# ardcore.net
KiCad netlist of a schematic drawn in EAGLE
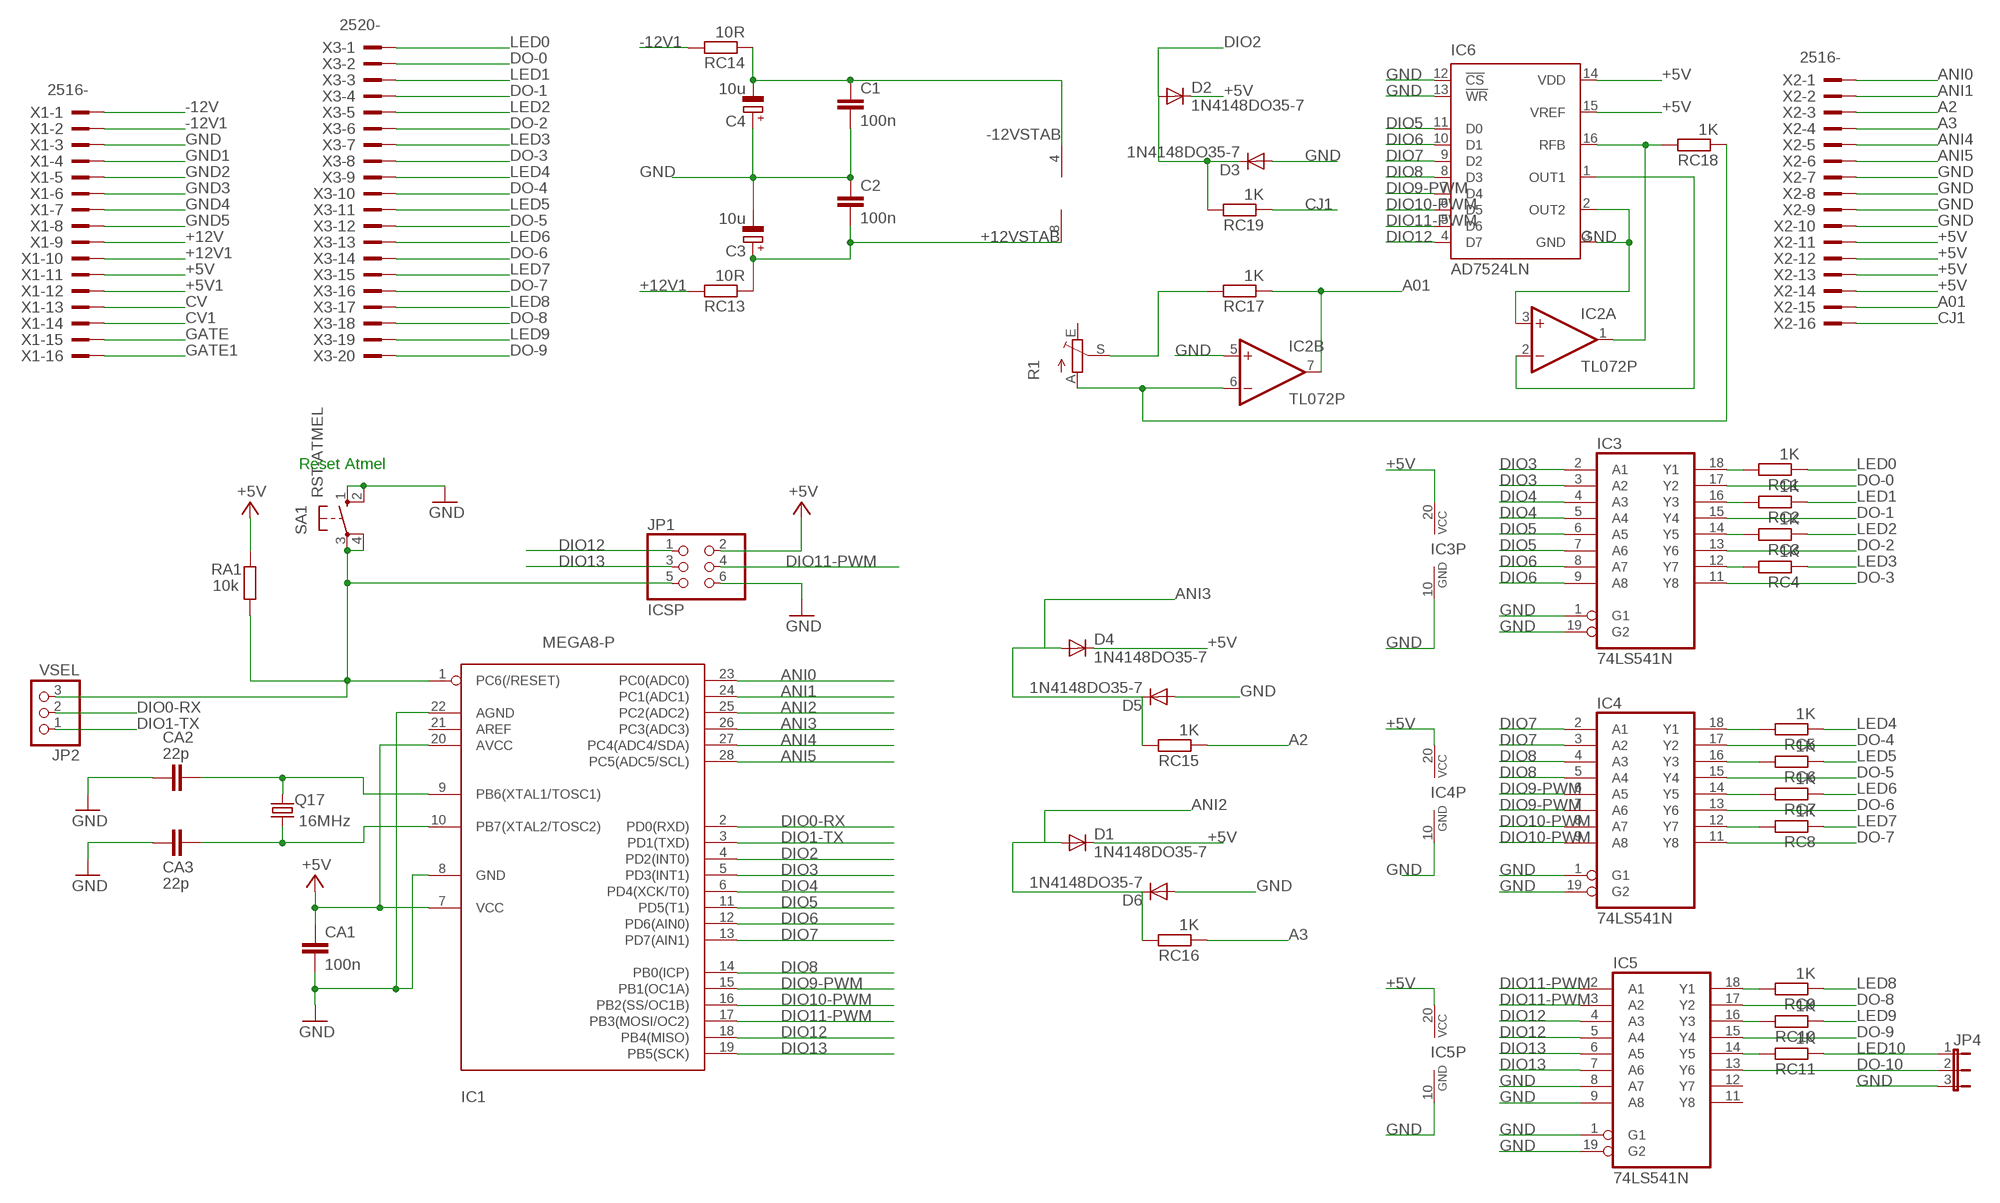
[diagram p0: schematic, sheet 1]

(export (version "E")
  (design (tool "Eeschema 10.0.6"))
  (components
    (comp (ref "C1")
      (value "100n")
      (footprint "eagle-import:C050-025X075")
      (libsource (lib "eagle-import") (part "C-EU050-025X075"))
    )
    (comp (ref "C2")
      (value "100n")
      (footprint "eagle-import:C050-025X075")
      (libsource (lib "eagle-import") (part "C-EU050-025X075"))
    )
    (comp (ref "C3")
      (value "10u")
      (footprint "eagle-import:E2,5-7")
      (libsource (lib "eagle-import") (part "CPOL-EUE2.5-7"))
    )
    (comp (ref "C4")
      (value "10u")
      (footprint "eagle-import:E2,5-7")
      (libsource (lib "eagle-import") (part "CPOL-EUE2.5-7"))
    )
    (comp (ref "CA1")
      (value "100n")
      (footprint "eagle-import:C050-025X075")
      (libsource (lib "eagle-import") (part "C-EU050-025X075"))
    )
    (comp (ref "CA2")
      (value "22p")
      (footprint "eagle-import:C050-025X075")
      (libsource (lib "eagle-import") (part "C-EU050-025X075"))
    )
    (comp (ref "CA3")
      (value "22p")
      (footprint "eagle-import:C050-025X075")
      (libsource (lib "eagle-import") (part "C-EU050-025X075"))
    )
    (comp (ref "D1")
      (value "1N4148DO35-7")
      (footprint "eagle-import:DO35-7")
      (libsource (lib "eagle-import") (part "1N4148DO35-7"))
    )
    (comp (ref "D2")
      (value "1N4148DO35-7")
      (footprint "eagle-import:DO35-7")
      (libsource (lib "eagle-import") (part "1N4148DO35-7"))
    )
    (comp (ref "D3")
      (value "1N4148DO35-7")
      (footprint "eagle-import:DO35-7")
      (libsource (lib "eagle-import") (part "1N4148DO35-7"))
    )
    (comp (ref "D4")
      (value "1N4148DO35-7")
      (footprint "eagle-import:DO35-7")
      (libsource (lib "eagle-import") (part "1N4148DO35-7"))
    )
    (comp (ref "D5")
      (value "1N4148DO35-7")
      (footprint "eagle-import:DO35-7")
      (libsource (lib "eagle-import") (part "1N4148DO35-7"))
    )
    (comp (ref "D6")
      (value "1N4148DO35-7")
      (footprint "eagle-import:DO35-7")
      (libsource (lib "eagle-import") (part "1N4148DO35-7"))
    )
    (comp (ref "IC1")
      (value "MEGA8-P")
      (footprint "eagle-import:DIL28-3")
      (libsource (lib "eagle-import") (part "MEGA8-P"))
    )
    (comp (ref "IC2")
      (value "TL072P")
      (footprint "eagle-import:DIL08")
      (libsource (lib "eagle-import") (part "TL072P"))
    )
    (comp (ref "IC3")
      (value "74LS541N")
      (footprint "eagle-import:DIL20")
      (libsource (lib "eagle-import") (part "74541NLS"))
    )
    (comp (ref "IC4")
      (value "74LS541N")
      (footprint "eagle-import:DIL20")
      (libsource (lib "eagle-import") (part "74541NLS"))
    )
    (comp (ref "IC5")
      (value "74LS541N")
      (footprint "eagle-import:DIL20")
      (libsource (lib "eagle-import") (part "74541NLS"))
    )
    (comp (ref "IC6")
      (value "AD7524LN")
      (footprint "eagle-import:DIL16")
      (fields (field (name "MF") "ALTERA CORPORATION") (field (name "MPN") "AD7524LNZ"))
      (libsource (lib "eagle-import") (part "AD7524NL"))
    )
    (comp (ref "JP1")
      (value "ICSP")
      (footprint "eagle-import:2X03")
      (libsource (lib "eagle-import") (part "PINHD-2X3"))
    )
    (comp (ref "JP2")
      (value "VSEL")
      (footprint "eagle-import:1X03")
      (libsource (lib "eagle-import") (part "PINHD-1X3"))
    )
    (comp (ref "JP4")
      (value "JP2E")
      (footprint "eagle-import:JP2")
      (libsource (lib "eagle-import") (part "JP2E"))
    )
    (comp (ref "Q17")
      (value "16MHz")
      (footprint "eagle-import:HC49_S")
      (libsource (lib "eagle-import") (part "CRYSTALHC49S"))
    )
    (comp (ref "R1")
      (value "TRIM_EU-B64Y")
      (footprint "eagle-import:B64Y")
      (libsource (lib "eagle-import") (part "TRIM_EU-B64Y"))
    )
    (comp (ref "RA1")
      (value "10k")
      (footprint "eagle-import:0207_10")
      (libsource (lib "eagle-import") (part "R-EU_0207/10"))
    )
    (comp (ref "RC1")
      (value "1K")
      (footprint "eagle-import:0207_10")
      (libsource (lib "eagle-import") (part "R-EU_0207/10"))
    )
    (comp (ref "RC2")
      (value "1K")
      (footprint "eagle-import:0207_10")
      (libsource (lib "eagle-import") (part "R-EU_0207/10"))
    )
    (comp (ref "RC3")
      (value "1K")
      (footprint "eagle-import:0207_10")
      (libsource (lib "eagle-import") (part "R-EU_0207/10"))
    )
    (comp (ref "RC4")
      (value "1K")
      (footprint "eagle-import:0207_10")
      (libsource (lib "eagle-import") (part "R-EU_0207/10"))
    )
    (comp (ref "RC5")
      (value "1K")
      (footprint "eagle-import:0207_10")
      (libsource (lib "eagle-import") (part "R-EU_0207/10"))
    )
    (comp (ref "RC6")
      (value "1K")
      (footprint "eagle-import:0207_10")
      (libsource (lib "eagle-import") (part "R-EU_0207/10"))
    )
    (comp (ref "RC7")
      (value "1K")
      (footprint "eagle-import:0207_10")
      (libsource (lib "eagle-import") (part "R-EU_0207/10"))
    )
    (comp (ref "RC8")
      (value "1K")
      (footprint "eagle-import:0207_10")
      (libsource (lib "eagle-import") (part "R-EU_0207/10"))
    )
    (comp (ref "RC9")
      (value "1K")
      (footprint "eagle-import:0207_10")
      (libsource (lib "eagle-import") (part "R-EU_0207/10"))
    )
    (comp (ref "RC10")
      (value "1K")
      (footprint "eagle-import:0207_10")
      (libsource (lib "eagle-import") (part "R-EU_0207/10"))
    )
    (comp (ref "RC11")
      (value "1K")
      (footprint "eagle-import:0207_10")
      (libsource (lib "eagle-import") (part "R-EU_0207/10"))
    )
    (comp (ref "RC13")
      (value "10R")
      (footprint "eagle-import:0207_10")
      (libsource (lib "eagle-import") (part "R-EU_0207/10"))
    )
    (comp (ref "RC14")
      (value "10R")
      (footprint "eagle-import:0207_10")
      (libsource (lib "eagle-import") (part "R-EU_0207/10"))
    )
    (comp (ref "RC15")
      (value "1K")
      (footprint "eagle-import:0207_10")
      (libsource (lib "eagle-import") (part "R-EU_0207/10"))
    )
    (comp (ref "RC16")
      (value "1K")
      (footprint "eagle-import:0207_10")
      (libsource (lib "eagle-import") (part "R-EU_0207/10"))
    )
    (comp (ref "RC17")
      (value "1K")
      (footprint "eagle-import:0207_10")
      (libsource (lib "eagle-import") (part "R-EU_0207/10"))
    )
    (comp (ref "RC18")
      (value "1K")
      (footprint "eagle-import:0207_10")
      (libsource (lib "eagle-import") (part "R-EU_0207/10"))
    )
    (comp (ref "RC19")
      (value "1K")
      (footprint "eagle-import:0207_10")
      (libsource (lib "eagle-import") (part "R-EU_0207/10"))
    )
    (comp (ref "SA1")
      (value "RST-ATMEL")
      (footprint "eagle-import:B3F-10XX")
      (libsource (lib "eagle-import") (part "10-XX"))
    )
    (comp (ref "X1")
      (value "2516-")
      (footprint "eagle-import:PAK100_2500-16")
      (libsource (lib "eagle-import") (part "2516-"))
    )
    (comp (ref "X2")
      (value "2516-")
      (footprint "eagle-import:PAK100_2500-16")
      (libsource (lib "eagle-import") (part "2516-"))
    )
    (comp (ref "X3")
      (value "2520-")
      (footprint "eagle-import:PAK100_2500-20")
      (libsource (lib "eagle-import") (part "2520-"))
    )
  )
  (nets
    (net (code "1") (name "+5V") (class "Default")
      (node (ref "CA1") (pin "1") (pinfunction "1_1") (pintype "passive"))
      (node (ref "D1") (pin "C") (pinfunction "C_C") (pintype "passive"))
      (node (ref "D2") (pin "C") (pinfunction "C_C") (pintype "passive"))
      (node (ref "D4") (pin "C") (pinfunction "C_C") (pintype "passive"))
      (node (ref "IC1") (pin "20") (pinfunction "AVCC_20") (pintype "power_in"))
      (node (ref "IC1") (pin "7") (pinfunction "VCC_7") (pintype "power_in"))
      (node (ref "IC3") (pin "20") (pinfunction "VCC_20") (pintype "power_in"))
      (node (ref "IC4") (pin "20") (pinfunction "VCC_20") (pintype "power_in"))
      (node (ref "IC5") (pin "20") (pinfunction "VCC_20") (pintype "power_in"))
      (node (ref "IC6") (pin "14") (pinfunction "VDD_14") (pintype "power_in"))
      (node (ref "IC6") (pin "15") (pinfunction "VREF_15") (pintype "input"))
      (node (ref "JP1") (pin "2") (pinfunction "2_2") (pintype "passive"))
      (node (ref "RA1") (pin "1") (pinfunction "1_1") (pintype "passive"))
      (node (ref "X1") (pin "11") (pinfunction "KL_11") (pintype "passive"))
      (node (ref "X2") (pin "11") (pinfunction "KL_11") (pintype "passive"))
      (node (ref "X2") (pin "12") (pinfunction "KL_12") (pintype "passive"))
      (node (ref "X2") (pin "13") (pinfunction "KL_13") (pintype "passive"))
      (node (ref "X2") (pin "14") (pinfunction "KL_14") (pintype "passive"))
    )
    (net (code "2") (name "/+5V1") (class "Default")
      (node (ref "X1") (pin "12") (pinfunction "KL_12") (pintype "passive"))
    )
    (net (code "3") (name "/+12V") (class "Default")
      (node (ref "X1") (pin "9") (pinfunction "KL_9") (pintype "passive"))
    )
    (net (code "4") (name "/+12V1") (class "Default")
      (node (ref "RC13") (pin "2") (pinfunction "2_2") (pintype "passive"))
      (node (ref "X1") (pin "10") (pinfunction "KL_10") (pintype "passive"))
    )
    (net (code "5") (name "/+12VSTAB") (class "Default")
      (node (ref "C2") (pin "2") (pinfunction "2_2") (pintype "passive"))
      (node (ref "C3") (pin "+") (pinfunction "+_+") (pintype "passive"))
      (node (ref "IC2") (pin "8") (pinfunction "V+_8") (pintype "power_in"))
      (node (ref "RC13") (pin "1") (pinfunction "1_1") (pintype "passive"))
    )
    (net (code "6") (name "/-12V") (class "Default")
      (node (ref "X1") (pin "1") (pinfunction "KL_1") (pintype "passive"))
    )
    (net (code "7") (name "/-12V1") (class "Default")
      (node (ref "RC14") (pin "2") (pinfunction "2_2") (pintype "passive"))
      (node (ref "X1") (pin "2") (pinfunction "KL_2") (pintype "passive"))
    )
    (net (code "8") (name "/-12VSTAB") (class "Default")
      (node (ref "C1") (pin "1") (pinfunction "1_1") (pintype "passive"))
      (node (ref "C4") (pin "-") (pinfunction "-_-") (pintype "passive"))
      (node (ref "IC2") (pin "4") (pinfunction "V-_4") (pintype "power_in"))
      (node (ref "RC14") (pin "1") (pinfunction "1_1") (pintype "passive"))
    )
    (net (code "9") (name "/A01") (class "Default")
      (node (ref "IC2") (pin "7") (pinfunction "OUT_7") (pintype "output"))
      (node (ref "RC17") (pin "1") (pinfunction "1_1") (pintype "passive"))
      (node (ref "X2") (pin "15") (pinfunction "KL_15") (pintype "passive"))
    )
    (net (code "10") (name "/A2") (class "Default")
      (node (ref "RC15") (pin "1") (pinfunction "1_1") (pintype "passive"))
      (node (ref "X2") (pin "3") (pinfunction "KL_3") (pintype "passive"))
    )
    (net (code "11") (name "/A3") (class "Default")
      (node (ref "RC16") (pin "1") (pinfunction "1_1") (pintype "passive"))
      (node (ref "X2") (pin "4") (pinfunction "KL_4") (pintype "passive"))
    )
    (net (code "12") (name "/ANI0") (class "Default")
      (node (ref "IC1") (pin "23") (pinfunction "PC0(ADC0)_23") (pintype "bidirectional"))
      (node (ref "X2") (pin "1") (pinfunction "KL_1") (pintype "passive"))
    )
    (net (code "13") (name "/ANI1") (class "Default")
      (node (ref "IC1") (pin "24") (pinfunction "PC1(ADC1)_24") (pintype "bidirectional"))
      (node (ref "X2") (pin "2") (pinfunction "KL_2") (pintype "passive"))
    )
    (net (code "14") (name "/ANI2") (class "Default")
      (node (ref "D1") (pin "A") (pinfunction "A_A") (pintype "passive"))
      (node (ref "D6") (pin "C") (pinfunction "C_C") (pintype "passive"))
      (node (ref "IC1") (pin "25") (pinfunction "PC2(ADC2)_25") (pintype "bidirectional"))
      (node (ref "RC16") (pin "2") (pinfunction "2_2") (pintype "passive"))
    )
    (net (code "15") (name "/ANI3") (class "Default")
      (node (ref "D4") (pin "A") (pinfunction "A_A") (pintype "passive"))
      (node (ref "D5") (pin "C") (pinfunction "C_C") (pintype "passive"))
      (node (ref "IC1") (pin "26") (pinfunction "PC3(ADC3)_26") (pintype "bidirectional"))
      (node (ref "RC15") (pin "2") (pinfunction "2_2") (pintype "passive"))
    )
    (net (code "16") (name "/ANI4") (class "Default")
      (node (ref "IC1") (pin "27") (pinfunction "PC4(ADC4/SDA)_27") (pintype "bidirectional"))
      (node (ref "X2") (pin "5") (pinfunction "KL_5") (pintype "passive"))
    )
    (net (code "17") (name "/ANI5") (class "Default")
      (node (ref "IC1") (pin "28") (pinfunction "PC5(ADC5/SCL)_28") (pintype "bidirectional"))
      (node (ref "X2") (pin "6") (pinfunction "KL_6") (pintype "passive"))
    )
    (net (code "18") (name "/CJ1") (class "Default")
      (node (ref "RC19") (pin "1") (pinfunction "1_1") (pintype "passive"))
      (node (ref "X2") (pin "16") (pinfunction "KL_16") (pintype "passive"))
    )
    (net (code "19") (name "/CV") (class "Default")
      (node (ref "X1") (pin "13") (pinfunction "KL_13") (pintype "passive"))
    )
    (net (code "20") (name "/CV1") (class "Default")
      (node (ref "X1") (pin "14") (pinfunction "KL_14") (pintype "passive"))
    )
    (net (code "21") (name "/DIO0-RX") (class "Default")
      (node (ref "IC1") (pin "2") (pinfunction "PD0(RXD)_2") (pintype "bidirectional"))
      (node (ref "JP2") (pin "2") (pinfunction "2_2") (pintype "passive"))
    )
    (net (code "22") (name "/DIO1-TX") (class "Default")
      (node (ref "IC1") (pin "3") (pinfunction "PD1(TXD)_3") (pintype "bidirectional"))
      (node (ref "JP2") (pin "1") (pinfunction "1_1") (pintype "passive"))
    )
    (net (code "23") (name "/DIO2") (class "Default")
      (node (ref "D2") (pin "A") (pinfunction "A_A") (pintype "passive"))
      (node (ref "D3") (pin "C") (pinfunction "C_C") (pintype "passive"))
      (node (ref "IC1") (pin "4") (pinfunction "PD2(INT0)_4") (pintype "bidirectional"))
      (node (ref "RC19") (pin "2") (pinfunction "2_2") (pintype "passive"))
    )
    (net (code "24") (name "/DIO3") (class "Default")
      (node (ref "IC1") (pin "5") (pinfunction "PD3(INT1)_5") (pintype "bidirectional"))
      (node (ref "IC3") (pin "2") (pinfunction "A1_2") (pintype "input"))
      (node (ref "IC3") (pin "3") (pinfunction "A2_3") (pintype "input"))
    )
    (net (code "25") (name "/DIO4") (class "Default")
      (node (ref "IC1") (pin "6") (pinfunction "PD4(XCK/T0)_6") (pintype "bidirectional"))
      (node (ref "IC3") (pin "4") (pinfunction "A3_4") (pintype "input"))
      (node (ref "IC3") (pin "5") (pinfunction "A4_5") (pintype "input"))
    )
    (net (code "26") (name "/DIO5") (class "Default")
      (node (ref "IC1") (pin "11") (pinfunction "PD5(T1)_11") (pintype "bidirectional"))
      (node (ref "IC3") (pin "6") (pinfunction "A5_6") (pintype "input"))
      (node (ref "IC3") (pin "7") (pinfunction "A6_7") (pintype "input"))
      (node (ref "IC6") (pin "11") (pinfunction "D0_11") (pintype "input"))
    )
    (net (code "27") (name "/DIO6") (class "Default")
      (node (ref "IC1") (pin "12") (pinfunction "PD6(AIN0)_12") (pintype "bidirectional"))
      (node (ref "IC3") (pin "8") (pinfunction "A7_8") (pintype "input"))
      (node (ref "IC3") (pin "9") (pinfunction "A8_9") (pintype "input"))
      (node (ref "IC6") (pin "10") (pinfunction "D1_10") (pintype "input"))
    )
    (net (code "28") (name "/DIO7") (class "Default")
      (node (ref "IC1") (pin "13") (pinfunction "PD7(AIN1)_13") (pintype "bidirectional"))
      (node (ref "IC4") (pin "2") (pinfunction "A1_2") (pintype "input"))
      (node (ref "IC4") (pin "3") (pinfunction "A2_3") (pintype "input"))
      (node (ref "IC6") (pin "9") (pinfunction "D2_9") (pintype "input"))
    )
    (net (code "29") (name "/DIO8") (class "Default")
      (node (ref "IC1") (pin "14") (pinfunction "PB0(ICP)_14") (pintype "bidirectional"))
      (node (ref "IC4") (pin "4") (pinfunction "A3_4") (pintype "input"))
      (node (ref "IC4") (pin "5") (pinfunction "A4_5") (pintype "input"))
      (node (ref "IC6") (pin "8") (pinfunction "D3_8") (pintype "input"))
    )
    (net (code "30") (name "/DIO9-PWM") (class "Default")
      (node (ref "IC1") (pin "15") (pinfunction "PB1(OC1A)_15") (pintype "bidirectional"))
      (node (ref "IC4") (pin "6") (pinfunction "A5_6") (pintype "input"))
      (node (ref "IC4") (pin "7") (pinfunction "A6_7") (pintype "input"))
      (node (ref "IC6") (pin "7") (pinfunction "D4_7") (pintype "input"))
    )
    (net (code "31") (name "/DIO10-PWM") (class "Default")
      (node (ref "IC1") (pin "16") (pinfunction "PB2(SS/OC1B)_16") (pintype "bidirectional"))
      (node (ref "IC4") (pin "8") (pinfunction "A7_8") (pintype "input"))
      (node (ref "IC4") (pin "9") (pinfunction "A8_9") (pintype "input"))
      (node (ref "IC6") (pin "6") (pinfunction "D5_6") (pintype "input"))
    )
    (net (code "32") (name "/DIO11-PWM") (class "Default")
      (node (ref "IC1") (pin "17") (pinfunction "PB3(MOSI/OC2)_17") (pintype "bidirectional"))
      (node (ref "IC5") (pin "2") (pinfunction "A1_2") (pintype "input"))
      (node (ref "IC5") (pin "3") (pinfunction "A2_3") (pintype "input"))
      (node (ref "IC6") (pin "5") (pinfunction "D6_5") (pintype "input"))
      (node (ref "JP1") (pin "4") (pinfunction "4_4") (pintype "passive"))
    )
    (net (code "33") (name "/DIO12") (class "Default")
      (node (ref "IC1") (pin "18") (pinfunction "PB4(MISO)_18") (pintype "bidirectional"))
      (node (ref "IC5") (pin "4") (pinfunction "A3_4") (pintype "input"))
      (node (ref "IC5") (pin "5") (pinfunction "A4_5") (pintype "input"))
      (node (ref "IC6") (pin "4") (pinfunction "D7_4") (pintype "input"))
      (node (ref "JP1") (pin "1") (pinfunction "1_1") (pintype "passive"))
    )
    (net (code "34") (name "/DIO13") (class "Default")
      (node (ref "IC1") (pin "19") (pinfunction "PB5(SCK)_19") (pintype "bidirectional"))
      (node (ref "IC5") (pin "6") (pinfunction "A5_6") (pintype "input"))
      (node (ref "IC5") (pin "7") (pinfunction "A6_7") (pintype "input"))
      (node (ref "JP1") (pin "3") (pinfunction "3_3") (pintype "passive"))
    )
    (net (code "35") (name "/DO-0") (class "Default")
      (node (ref "IC3") (pin "17") (pinfunction "Y2_17") (pintype "tri_state"))
      (node (ref "X3") (pin "2") (pinfunction "KL_2") (pintype "passive"))
    )
    (net (code "36") (name "/DO-1") (class "Default")
      (node (ref "IC3") (pin "15") (pinfunction "Y4_15") (pintype "tri_state"))
      (node (ref "X3") (pin "4") (pinfunction "KL_4") (pintype "passive"))
    )
    (net (code "37") (name "/DO-2") (class "Default")
      (node (ref "IC3") (pin "13") (pinfunction "Y6_13") (pintype "tri_state"))
      (node (ref "X3") (pin "6") (pinfunction "KL_6") (pintype "passive"))
    )
    (net (code "38") (name "/DO-3") (class "Default")
      (node (ref "IC3") (pin "11") (pinfunction "Y8_11") (pintype "tri_state"))
      (node (ref "X3") (pin "8") (pinfunction "KL_8") (pintype "passive"))
    )
    (net (code "39") (name "/DO-4") (class "Default")
      (node (ref "IC4") (pin "17") (pinfunction "Y2_17") (pintype "tri_state"))
      (node (ref "X3") (pin "10") (pinfunction "KL_10") (pintype "passive"))
    )
    (net (code "40") (name "/DO-5") (class "Default")
      (node (ref "IC4") (pin "15") (pinfunction "Y4_15") (pintype "tri_state"))
      (node (ref "X3") (pin "12") (pinfunction "KL_12") (pintype "passive"))
    )
    (net (code "41") (name "/DO-6") (class "Default")
      (node (ref "IC4") (pin "13") (pinfunction "Y6_13") (pintype "tri_state"))
      (node (ref "X3") (pin "14") (pinfunction "KL_14") (pintype "passive"))
    )
    (net (code "42") (name "/DO-7") (class "Default")
      (node (ref "IC4") (pin "11") (pinfunction "Y8_11") (pintype "tri_state"))
      (node (ref "X3") (pin "16") (pinfunction "KL_16") (pintype "passive"))
    )
    (net (code "43") (name "/DO-8") (class "Default")
      (node (ref "IC5") (pin "17") (pinfunction "Y2_17") (pintype "tri_state"))
      (node (ref "X3") (pin "18") (pinfunction "KL_18") (pintype "passive"))
    )
    (net (code "44") (name "/DO-9") (class "Default")
      (node (ref "IC5") (pin "15") (pinfunction "Y4_15") (pintype "tri_state"))
      (node (ref "X3") (pin "20") (pinfunction "KL_20") (pintype "passive"))
    )
    (net (code "45") (name "/DO-10") (class "Default")
      (node (ref "IC5") (pin "13") (pinfunction "Y6_13") (pintype "tri_state"))
      (node (ref "JP4") (pin "2") (pinfunction "2_2") (pintype "passive"))
    )
    (net (code "46") (name "/GATE") (class "Default")
      (node (ref "X1") (pin "15") (pinfunction "KL_15") (pintype "passive"))
    )
    (net (code "47") (name "/GATE1") (class "Default")
      (node (ref "X1") (pin "16") (pinfunction "KL_16") (pintype "passive"))
    )
    (net (code "48") (name "/GND1") (class "Default")
      (node (ref "X1") (pin "4") (pinfunction "KL_4") (pintype "passive"))
    )
    (net (code "49") (name "/GND2") (class "Default")
      (node (ref "X1") (pin "5") (pinfunction "KL_5") (pintype "passive"))
    )
    (net (code "50") (name "/GND3") (class "Default")
      (node (ref "X1") (pin "6") (pinfunction "KL_6") (pintype "passive"))
    )
    (net (code "51") (name "/GND4") (class "Default")
      (node (ref "X1") (pin "7") (pinfunction "KL_7") (pintype "passive"))
    )
    (net (code "52") (name "/GND5") (class "Default")
      (node (ref "X1") (pin "8") (pinfunction "KL_8") (pintype "passive"))
    )
    (net (code "53") (name "/LED0") (class "Default")
      (node (ref "RC1") (pin "1") (pinfunction "1_1") (pintype "passive"))
      (node (ref "X3") (pin "1") (pinfunction "KL_1") (pintype "passive"))
    )
    (net (code "54") (name "/LED1") (class "Default")
      (node (ref "RC2") (pin "1") (pinfunction "1_1") (pintype "passive"))
      (node (ref "X3") (pin "3") (pinfunction "KL_3") (pintype "passive"))
    )
    (net (code "55") (name "/LED2") (class "Default")
      (node (ref "RC3") (pin "1") (pinfunction "1_1") (pintype "passive"))
      (node (ref "X3") (pin "5") (pinfunction "KL_5") (pintype "passive"))
    )
    (net (code "56") (name "/LED3") (class "Default")
      (node (ref "RC4") (pin "1") (pinfunction "1_1") (pintype "passive"))
      (node (ref "X3") (pin "7") (pinfunction "KL_7") (pintype "passive"))
    )
    (net (code "57") (name "/LED4") (class "Default")
      (node (ref "RC5") (pin "1") (pinfunction "1_1") (pintype "passive"))
      (node (ref "X3") (pin "9") (pinfunction "KL_9") (pintype "passive"))
    )
    (net (code "58") (name "/LED5") (class "Default")
      (node (ref "RC6") (pin "1") (pinfunction "1_1") (pintype "passive"))
      (node (ref "X3") (pin "11") (pinfunction "KL_11") (pintype "passive"))
    )
    (net (code "59") (name "/LED6") (class "Default")
      (node (ref "RC7") (pin "1") (pinfunction "1_1") (pintype "passive"))
      (node (ref "X3") (pin "13") (pinfunction "KL_13") (pintype "passive"))
    )
    (net (code "60") (name "/LED7") (class "Default")
      (node (ref "RC8") (pin "1") (pinfunction "1_1") (pintype "passive"))
      (node (ref "X3") (pin "15") (pinfunction "KL_15") (pintype "passive"))
    )
    (net (code "61") (name "/LED8") (class "Default")
      (node (ref "RC9") (pin "1") (pinfunction "1_1") (pintype "passive"))
      (node (ref "X3") (pin "17") (pinfunction "KL_17") (pintype "passive"))
    )
    (net (code "62") (name "/LED9") (class "Default")
      (node (ref "RC10") (pin "1") (pinfunction "1_1") (pintype "passive"))
      (node (ref "X3") (pin "19") (pinfunction "KL_19") (pintype "passive"))
    )
    (net (code "63") (name "/LED10") (class "Default")
      (node (ref "JP4") (pin "1") (pinfunction "1_1") (pintype "passive"))
      (node (ref "RC11") (pin "1") (pinfunction "1_1") (pintype "passive"))
    )
    (net (code "64") (name "GND") (class "Default")
      (node (ref "C1") (pin "2") (pinfunction "2_2") (pintype "passive"))
      (node (ref "C2") (pin "1") (pinfunction "1_1") (pintype "passive"))
      (node (ref "C3") (pin "-") (pinfunction "-_-") (pintype "passive"))
      (node (ref "C4") (pin "+") (pinfunction "+_+") (pintype "passive"))
      (node (ref "CA1") (pin "2") (pinfunction "2_2") (pintype "passive"))
      (node (ref "CA2") (pin "2") (pinfunction "2_2") (pintype "passive"))
      (node (ref "CA3") (pin "2") (pinfunction "2_2") (pintype "passive"))
      (node (ref "D3") (pin "A") (pinfunction "A_A") (pintype "passive"))
      (node (ref "D5") (pin "A") (pinfunction "A_A") (pintype "passive"))
      (node (ref "D6") (pin "A") (pinfunction "A_A") (pintype "passive"))
      (node (ref "IC1") (pin "22") (pinfunction "AGND_22") (pintype "power_in"))
      (node (ref "IC1") (pin "8") (pinfunction "GND_8") (pintype "power_in"))
      (node (ref "IC2") (pin "3") (pinfunction "+IN_3") (pintype "input"))
      (node (ref "IC2") (pin "5") (pinfunction "+IN_5") (pintype "input"))
      (node (ref "IC3") (pin "1") (pinfunction "G1_1") (pintype "input"))
      (node (ref "IC3") (pin "10") (pinfunction "GND_10") (pintype "power_in"))
      (node (ref "IC3") (pin "19") (pinfunction "G2_19") (pintype "input"))
      (node (ref "IC4") (pin "1") (pinfunction "G1_1") (pintype "input"))
      (node (ref "IC4") (pin "10") (pinfunction "GND_10") (pintype "power_in"))
      (node (ref "IC4") (pin "19") (pinfunction "G2_19") (pintype "input"))
      (node (ref "IC5") (pin "1") (pinfunction "G1_1") (pintype "input"))
      (node (ref "IC5") (pin "10") (pinfunction "GND_10") (pintype "power_in"))
      (node (ref "IC5") (pin "19") (pinfunction "G2_19") (pintype "input"))
      (node (ref "IC5") (pin "8") (pinfunction "A7_8") (pintype "input"))
      (node (ref "IC5") (pin "9") (pinfunction "A8_9") (pintype "input"))
      (node (ref "IC6") (pin "12") (pinfunction "~{CS}_12") (pintype "input"))
      (node (ref "IC6") (pin "13") (pinfunction "~{WR}_13") (pintype "input"))
      (node (ref "IC6") (pin "2") (pinfunction "OUT2_2") (pintype "passive"))
      (node (ref "IC6") (pin "3") (pinfunction "GND_3") (pintype "power_in"))
      (node (ref "JP1") (pin "6") (pinfunction "6_6") (pintype "passive"))
      (node (ref "JP4") (pin "3") (pinfunction "3_3") (pintype "passive"))
      (node (ref "SA1") (pin "1") (pinfunction "S_1") (pintype "passive"))
      (node (ref "SA1") (pin "2") (pinfunction "S1_2") (pintype "passive"))
      (node (ref "X1") (pin "3") (pinfunction "KL_3") (pintype "passive"))
      (node (ref "X2") (pin "10") (pinfunction "KL_10") (pintype "passive"))
      (node (ref "X2") (pin "7") (pinfunction "KL_7") (pintype "passive"))
      (node (ref "X2") (pin "8") (pinfunction "KL_8") (pintype "passive"))
      (node (ref "X2") (pin "9") (pinfunction "KL_9") (pintype "passive"))
    )
    (net (code "65") (name "Net-(IC1-PB6(XTAL1{slash}TOSC1))") (class "Default")
      (node (ref "CA2") (pin "1") (pinfunction "1_1") (pintype "passive"))
      (node (ref "IC1") (pin "9") (pinfunction "PB6(XTAL1/TOSC1)_9") (pintype "bidirectional"))
      (node (ref "Q17") (pin "2") (pinfunction "2_2") (pintype "passive"))
    )
    (net (code "66") (name "Net-(IC1-PB7(XTAL2{slash}TOSC2))") (class "Default")
      (node (ref "CA3") (pin "1") (pinfunction "1_1") (pintype "passive"))
      (node (ref "IC1") (pin "10") (pinfunction "PB7(XTAL2/TOSC2)_10") (pintype "bidirectional"))
      (node (ref "Q17") (pin "1") (pinfunction "1_1") (pintype "passive"))
    )
    (net (code "67") (name "Net-(IC1-PC6({slash}RESET))") (class "Default")
      (node (ref "IC1") (pin "1") (pinfunction "PC6(/RESET)_1") (pintype "bidirectional"))
      (node (ref "JP1") (pin "5") (pinfunction "5_5") (pintype "passive"))
      (node (ref "JP2") (pin "3") (pinfunction "3_3") (pintype "passive"))
      (node (ref "RA1") (pin "2") (pinfunction "2_2") (pintype "passive"))
      (node (ref "SA1") (pin "3") (pinfunction "P_3") (pintype "passive"))
      (node (ref "SA1") (pin "4") (pinfunction "P1_4") (pintype "passive"))
    )
    (net (code "68") (name "Net-(IC2A--IN)") (class "Default")
      (node (ref "IC2") (pin "2") (pinfunction "-IN_2") (pintype "input"))
      (node (ref "IC6") (pin "1") (pinfunction "OUT1_1") (pintype "passive"))
    )
    (net (code "69") (name "Net-(IC2A-OUT)") (class "Default")
      (node (ref "IC2") (pin "1") (pinfunction "OUT_1") (pintype "output"))
      (node (ref "IC6") (pin "16") (pinfunction "RFB_16") (pintype "passive"))
      (node (ref "RC18") (pin "2") (pinfunction "2_2") (pintype "passive"))
    )
    (net (code "70") (name "Net-(IC2B--IN)") (class "Default")
      (node (ref "IC2") (pin "6") (pinfunction "-IN_6") (pintype "input"))
      (node (ref "R1") (pin "A") (pinfunction "A_A") (pintype "passive"))
      (node (ref "RC18") (pin "1") (pinfunction "1_1") (pintype "passive"))
    )
    (net (code "71") (name "Net-(IC3A-Y1)") (class "Default")
      (node (ref "IC3") (pin "18") (pinfunction "Y1_18") (pintype "tri_state"))
      (node (ref "RC1") (pin "2") (pinfunction "2_2") (pintype "passive"))
    )
    (net (code "72") (name "Net-(IC3A-Y3)") (class "Default")
      (node (ref "IC3") (pin "16") (pinfunction "Y3_16") (pintype "tri_state"))
      (node (ref "RC2") (pin "2") (pinfunction "2_2") (pintype "passive"))
    )
    (net (code "73") (name "Net-(IC3A-Y5)") (class "Default")
      (node (ref "IC3") (pin "14") (pinfunction "Y5_14") (pintype "tri_state"))
      (node (ref "RC3") (pin "2") (pinfunction "2_2") (pintype "passive"))
    )
    (net (code "74") (name "Net-(IC3A-Y7)") (class "Default")
      (node (ref "IC3") (pin "12") (pinfunction "Y7_12") (pintype "tri_state"))
      (node (ref "RC4") (pin "2") (pinfunction "2_2") (pintype "passive"))
    )
    (net (code "75") (name "Net-(IC4A-Y1)") (class "Default")
      (node (ref "IC4") (pin "18") (pinfunction "Y1_18") (pintype "tri_state"))
      (node (ref "RC5") (pin "2") (pinfunction "2_2") (pintype "passive"))
    )
    (net (code "76") (name "Net-(IC4A-Y3)") (class "Default")
      (node (ref "IC4") (pin "16") (pinfunction "Y3_16") (pintype "tri_state"))
      (node (ref "RC6") (pin "2") (pinfunction "2_2") (pintype "passive"))
    )
    (net (code "77") (name "Net-(IC4A-Y5)") (class "Default")
      (node (ref "IC4") (pin "14") (pinfunction "Y5_14") (pintype "tri_state"))
      (node (ref "RC7") (pin "2") (pinfunction "2_2") (pintype "passive"))
    )
    (net (code "78") (name "Net-(IC4A-Y7)") (class "Default")
      (node (ref "IC4") (pin "12") (pinfunction "Y7_12") (pintype "tri_state"))
      (node (ref "RC8") (pin "2") (pinfunction "2_2") (pintype "passive"))
    )
    (net (code "79") (name "Net-(IC5A-Y1)") (class "Default")
      (node (ref "IC5") (pin "18") (pinfunction "Y1_18") (pintype "tri_state"))
      (node (ref "RC9") (pin "2") (pinfunction "2_2") (pintype "passive"))
    )
    (net (code "80") (name "Net-(IC5A-Y3)") (class "Default")
      (node (ref "IC5") (pin "16") (pinfunction "Y3_16") (pintype "tri_state"))
      (node (ref "RC10") (pin "2") (pinfunction "2_2") (pintype "passive"))
    )
    (net (code "81") (name "Net-(IC5A-Y5)") (class "Default")
      (node (ref "IC5") (pin "14") (pinfunction "Y5_14") (pintype "tri_state"))
      (node (ref "RC11") (pin "2") (pinfunction "2_2") (pintype "passive"))
    )
    (net (code "82") (name "Net-(R1-PadS)") (class "Default")
      (node (ref "R1") (pin "S") (pinfunction "S_S") (pintype "passive"))
      (node (ref "RC17") (pin "2") (pinfunction "2_2") (pintype "passive"))
    )
    (net (code "83") (name "unconnected-(IC1-AREF-Pad21)") (class "Default")
      (node (ref "IC1") (pin "21") (pinfunction "AREF_21") (pintype "passive"))
    )
    (net (code "84") (name "unconnected-(IC5A-Y7-Pad12)") (class "Default")
      (node (ref "IC5") (pin "12") (pinfunction "Y7_12") (pintype "tri_state"))
    )
    (net (code "85") (name "unconnected-(IC5A-Y8-Pad11)") (class "Default")
      (node (ref "IC5") (pin "11") (pinfunction "Y8_11") (pintype "tri_state"))
    )
    (net (code "86") (name "unconnected-(R1-PadE)") (class "Default")
      (node (ref "R1") (pin "E") (pinfunction "E_E") (pintype "passive"))
    )
  )
)
